# Sensor.net
KiCad netlist of a schematic drawn in Altium Designer
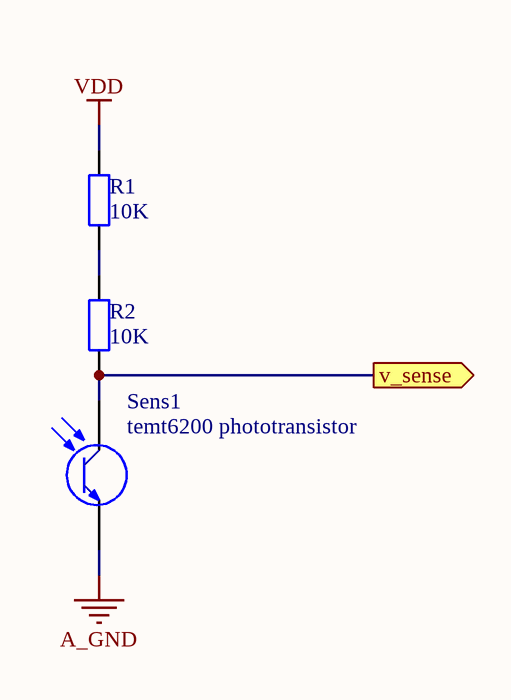
[diagram p0: Sensor.SchDoc]

(export (version "E")
  (design (tool "Eeschema 10.0.6"))
  (components
    (comp (ref "R1") (value "10K") (description "Resistor") (libsource (lib "EceParts") (part "Resistor")))
    (comp (ref "R2") (value "10K") (description "Resistor") (libsource (lib "EceParts") (part "Resistor")))
    (comp (ref "Sens1")
      (value "temt6200 phototransistor")
      (footprint "ECE-SENSOR-0805SM")
      (description "Light Sensor TEMT6200")
      (libsource (lib "EceParts") (part "TEMT6200"))
    )
  )
  (nets
    (net (code "1") (name "/v_sense") (class "Default")
      (node (ref "R2") (pin "1") (pinfunction "1_1") (pintype "passive"))
      (node (ref "Sens1") (pin "2") (pinfunction "C_2") (pintype "passive"))
    )
    (net (code "2") (name "A_GND") (class "Default")
      (node (ref "Sens1") (pin "1") (pinfunction "E_1") (pintype "passive"))
    )
    (net (code "3") (name "Net-(R1-Pad1)") (class "Default")
      (node (ref "R1") (pin "1") (pinfunction "1_1") (pintype "passive"))
      (node (ref "R2") (pin "2") (pinfunction "2_2") (pintype "passive"))
    )
    (net (code "4") (name "VDD") (class "Default")
      (node (ref "R1") (pin "2") (pinfunction "2_2") (pintype "passive"))
    )
  )
)
